# hev-controller_1_1.net
KiCad netlist of a schematic drawn in EAGLE
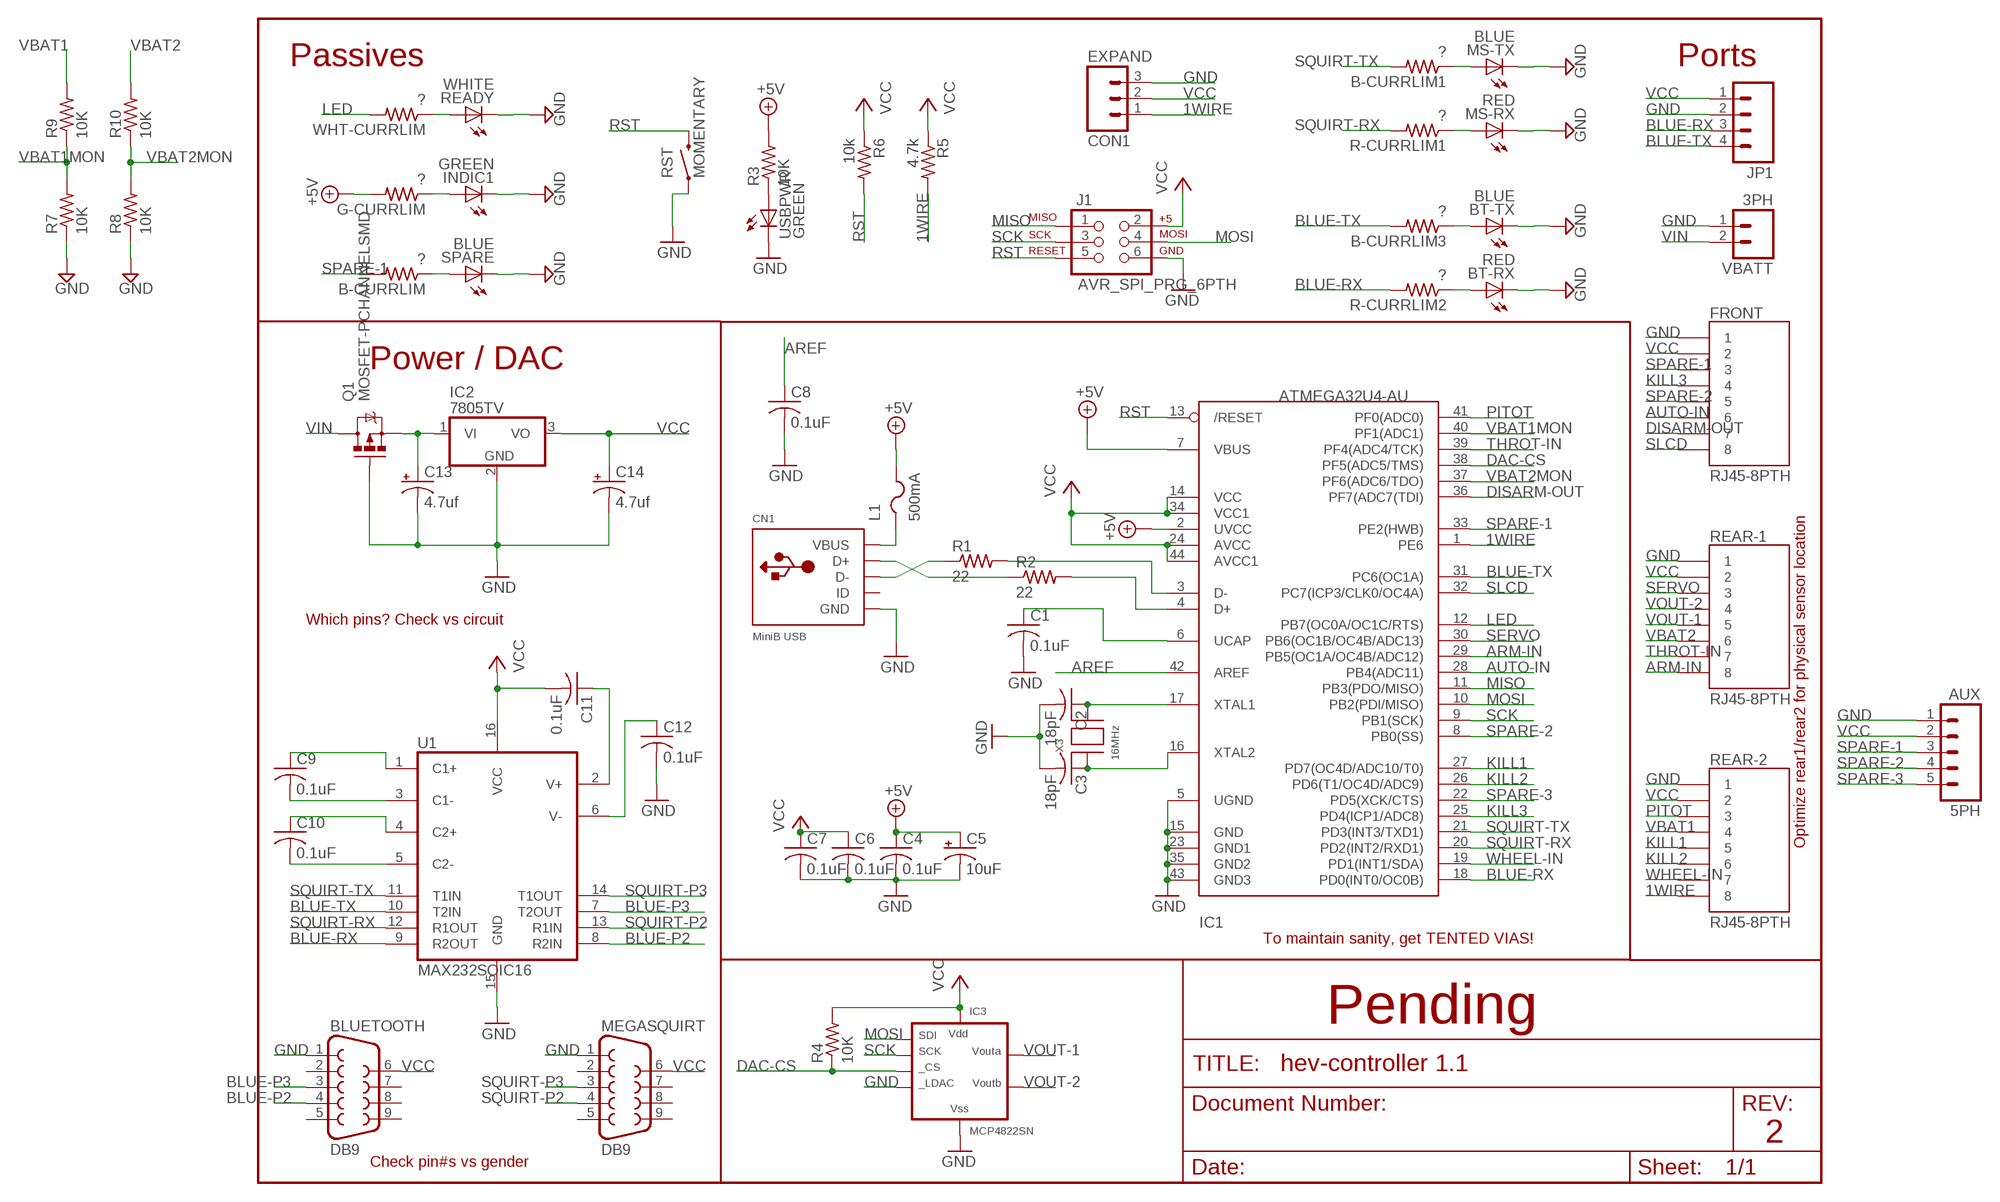
[diagram p0: schematic, sheet 1]

(export (version "E")
  (design (tool "Eeschema 10.0.6"))
  (components
    (comp (ref "5PH")
      (value "AUX")
      (footprint "eagle-import:1X05")
      (libsource (lib "eagle-import") (part "M05PTH"))
    )
    (comp (ref "B-CURRLIM")
      (value "?")
      (footprint "eagle-import:R0805")
      (libsource (lib "eagle-import") (part "R-US_R0805"))
    )
    (comp (ref "B-CURRLIM1")
      (value "?")
      (footprint "eagle-import:R0805")
      (libsource (lib "eagle-import") (part "R-US_R0805"))
    )
    (comp (ref "B-CURRLIM3")
      (value "?")
      (footprint "eagle-import:R0805")
      (libsource (lib "eagle-import") (part "R-US_R0805"))
    )
    (comp (ref "BLUETOOTH")
      (value "DB9")
      (footprint "eagle-import:DB9")
      (libsource (lib "eagle-import") (part "DB9"))
    )
    (comp (ref "BT-RX")
      (value "RED")
      (footprint "eagle-import:CHIPLED_0805")
      (libsource (lib "eagle-import") (part "LEDCHIPLED_0805"))
    )
    (comp (ref "BT-TX")
      (value "BLUE")
      (footprint "eagle-import:CHIPLED_0805")
      (libsource (lib "eagle-import") (part "LEDCHIPLED_0805"))
    )
    (comp (ref "C1")
      (value "0.1uF")
      (footprint "eagle-import:C0805K")
      (libsource (lib "eagle-import") (part "C-USC0805K"))
    )
    (comp (ref "C2")
      (value "18pF")
      (footprint "eagle-import:C0805K")
      (libsource (lib "eagle-import") (part "C-USC0805K"))
    )
    (comp (ref "C3")
      (value "18pF")
      (footprint "eagle-import:C0805K")
      (libsource (lib "eagle-import") (part "C-USC0805K"))
    )
    (comp (ref "C4")
      (value "0.1uF")
      (footprint "eagle-import:C0805K")
      (libsource (lib "eagle-import") (part "C-USC0805K"))
    )
    (comp (ref "C5")
      (value "10uF")
      (footprint "eagle-import:A_3216-18R")
      (libsource (lib "eagle-import") (part "CPOL-USA/3216-18R"))
    )
    (comp (ref "C6")
      (value "0.1uF")
      (footprint "eagle-import:C0805K")
      (libsource (lib "eagle-import") (part "C-USC0805K"))
    )
    (comp (ref "C7")
      (value "0.1uF")
      (footprint "eagle-import:C0805K")
      (libsource (lib "eagle-import") (part "C-USC0805K"))
    )
    (comp (ref "C8")
      (value "0.1uF")
      (footprint "eagle-import:C0805K")
      (libsource (lib "eagle-import") (part "C-USC0805K"))
    )
    (comp (ref "C9")
      (value "0.1uF")
      (footprint "eagle-import:C0805K")
      (libsource (lib "eagle-import") (part "C-USC0805K"))
    )
    (comp (ref "C10")
      (value "0.1uF")
      (footprint "eagle-import:C0805K")
      (libsource (lib "eagle-import") (part "C-USC0805K"))
    )
    (comp (ref "C11")
      (value "0.1uF")
      (footprint "eagle-import:C0805K")
      (libsource (lib "eagle-import") (part "C-USC0805K"))
    )
    (comp (ref "C12")
      (value "0.1uF")
      (footprint "eagle-import:C0805K")
      (libsource (lib "eagle-import") (part "C-USC0805K"))
    )
    (comp (ref "C13")
      (value "4.7uf")
      (footprint "eagle-import:E2,5-6")
      (libsource (lib "eagle-import") (part "rcl_CPOL-USE2.5-6"))
    )
    (comp (ref "C14")
      (value "4.7uf")
      (footprint "eagle-import:E2,5-6")
      (libsource (lib "eagle-import") (part "rcl_CPOL-USE2.5-6"))
    )
    (comp (ref "CN1")
      (value "MiniB USB")
      (footprint "eagle-import:USB-MINIB")
      (libsource (lib "eagle-import") (part "USBMINIB"))
    )
    (comp (ref "EXPAND")
      (value "CON1")
      (footprint "eagle-import:MOLEX-1X3")
      (libsource (lib "eagle-import") (part "M03POLAR"))
    )
    (comp (ref "FRONT")
      (value "RJ45-8PTH")
      (footprint "eagle-import:RJ45-8")
      (libsource (lib "eagle-import") (part "RJ45-8PTH"))
    )
    (comp (ref "G-CURRLIM")
      (value "?")
      (footprint "eagle-import:R0805")
      (libsource (lib "eagle-import") (part "R-US_R0805"))
    )
    (comp (ref "IC1")
      (value "ATMEGA32U4-AU")
      (footprint "eagle-import:TQFP44")
      (libsource (lib "eagle-import") (part "ATMEGA32U4-AU"))
    )
    (comp (ref "IC2")
      (value "7805TV")
      (footprint "eagle-import:TO220V")
      (libsource (lib "eagle-import") (part "78TV05"))
    )
    (comp (ref "IC3")
      (value "MCP4822SN")
      (footprint "eagle-import:SO-08")
      (libsource (lib "eagle-import") (part "MCP4822SN"))
    )
    (comp (ref "INDIC1")
      (value "GREEN")
      (footprint "eagle-import:CHIPLED_0805")
      (libsource (lib "eagle-import") (part "LEDCHIPLED_0805"))
    )
    (comp (ref "J1")
      (value "AVR_SPI_PRG_6PTH")
      (footprint "eagle-import:2X3")
      (libsource (lib "eagle-import") (part "AVR_SPI_PRG_6PTH"))
    )
    (comp (ref "JP1")
      (value "M04PTH")
      (footprint "eagle-import:1X04")
      (libsource (lib "eagle-import") (part "M04PTH"))
    )
    (comp (ref "L1")
      (value "500mA")
      (footprint "eagle-import:R1206")
      (libsource (lib "eagle-import") (part "PTCFUSE-1206"))
    )
    (comp (ref "MEGASQUIRT")
      (value "DB9")
      (footprint "eagle-import:DB9")
      (libsource (lib "eagle-import") (part "DB9"))
    )
    (comp (ref "MS-RX")
      (value "RED")
      (footprint "eagle-import:CHIPLED_0805")
      (libsource (lib "eagle-import") (part "LEDCHIPLED_0805"))
    )
    (comp (ref "MS-TX")
      (value "BLUE")
      (footprint "eagle-import:CHIPLED_0805")
      (libsource (lib "eagle-import") (part "LEDCHIPLED_0805"))
    )
    (comp (ref "Q1")
      (value "MOSFET-PCHANNELSMD")
      (footprint "eagle-import:SOT23-3")
      (libsource (lib "eagle-import") (part "MOSFET-PCHANNELSMD"))
    )
    (comp (ref "R-CURRLIM1")
      (value "?")
      (footprint "eagle-import:R0805")
      (libsource (lib "eagle-import") (part "R-US_R0805"))
    )
    (comp (ref "R-CURRLIM2")
      (value "?")
      (footprint "eagle-import:R0805")
      (libsource (lib "eagle-import") (part "R-US_R0805"))
    )
    (comp (ref "R1")
      (value "22")
      (footprint "eagle-import:R0805")
      (libsource (lib "eagle-import") (part "R-US_R0805"))
    )
    (comp (ref "R2")
      (value "22")
      (footprint "eagle-import:R0805")
      (libsource (lib "eagle-import") (part "R-US_R0805"))
    )
    (comp (ref "R3")
      (value "10K")
      (footprint "eagle-import:R0805")
      (libsource (lib "eagle-import") (part "R-US_R0805"))
    )
    (comp (ref "R4")
      (value "10K")
      (footprint "eagle-import:R0805")
      (libsource (lib "eagle-import") (part "R-US_R0805"))
    )
    (comp (ref "R5")
      (value "4.7k")
      (footprint "eagle-import:R0805")
      (libsource (lib "eagle-import") (part "R-US_R0805"))
    )
    (comp (ref "R6")
      (value "10k")
      (footprint "eagle-import:R0805")
      (libsource (lib "eagle-import") (part "R-US_R0805"))
    )
    (comp (ref "R7")
      (value "10K")
      (footprint "eagle-import:R0805")
      (libsource (lib "eagle-import") (part "R-US_R0805"))
    )
    (comp (ref "R8")
      (value "10K")
      (footprint "eagle-import:R0805")
      (libsource (lib "eagle-import") (part "R-US_R0805"))
    )
    (comp (ref "R9")
      (value "10K")
      (footprint "eagle-import:R0805")
      (libsource (lib "eagle-import") (part "R-US_R0805"))
    )
    (comp (ref "R10")
      (value "10K")
      (footprint "eagle-import:R0805")
      (libsource (lib "eagle-import") (part "R-US_R0805"))
    )
    (comp (ref "READY")
      (value "WHITE")
      (footprint "eagle-import:LED-1206")
      (libsource (lib "eagle-import") (part "LED1206"))
    )
    (comp (ref "REAR-1")
      (value "RJ45-8PTH")
      (footprint "eagle-import:RJ45-8")
      (libsource (lib "eagle-import") (part "RJ45-8PTH"))
    )
    (comp (ref "REAR-2")
      (value "RJ45-8PTH")
      (footprint "eagle-import:RJ45-8")
      (libsource (lib "eagle-import") (part "RJ45-8PTH"))
    )
    (comp (ref "RST")
      (value "MOMENTARY")
      (footprint "eagle-import:TACTILE-SWITCH-1101NE")
      (libsource (lib "eagle-import") (part "SWITCH-MOMENTARY-2-SMD-1101NE"))
    )
    (comp (ref "SPARE")
      (value "BLUE")
      (footprint "eagle-import:CHIPLED_0805")
      (libsource (lib "eagle-import") (part "LEDCHIPLED_0805"))
    )
    (comp (ref "U1")
      (value "MAX232SOIC16")
      (footprint "eagle-import:SO016")
      (libsource (lib "eagle-import") (part "MAX232SOIC16"))
    )
    (comp (ref "USBPWR")
      (value "GREEN")
      (footprint "eagle-import:CHIPLED_0805")
      (libsource (lib "eagle-import") (part "LEDCHIPLED_0805"))
    )
    (comp (ref "VBATT")
      (value "3PH")
      (footprint "eagle-import:SCREWTERMINAL-3.5MM-2")
      (libsource (lib "eagle-import") (part "M023.5MM"))
    )
    (comp (ref "WHT-CURRLIM")
      (value "?")
      (footprint "eagle-import:R0805")
      (libsource (lib "eagle-import") (part "R-US_R0805"))
    )
    (comp (ref "X3")
      (value "16MHz")
      (footprint "eagle-import:NX5032")
      (libsource (lib "eagle-import") (part "XTALNX5032"))
    )
  )
  (nets
    (net (code "1") (name "+5V") (class "Default")
      (node (ref "C4") (pin "1") (pinfunction "1_1") (pintype "passive"))
      (node (ref "C5") (pin "+") (pinfunction "+_+") (pintype "passive"))
      (node (ref "G-CURRLIM") (pin "2") (pinfunction "2_2") (pintype "passive"))
      (node (ref "IC1") (pin "2") (pinfunction "UVCC_2") (pintype "bidirectional"))
      (node (ref "IC1") (pin "7") (pinfunction "VBUS_7") (pintype "bidirectional"))
      (node (ref "L1") (pin "2") (pinfunction "2_2") (pintype "passive"))
      (node (ref "R3") (pin "2") (pinfunction "2_2") (pintype "passive"))
    )
    (net (code "2") (name "/1WIRE") (class "Default")
      (node (ref "EXPAND") (pin "1") (pinfunction "1_1") (pintype "passive"))
      (node (ref "IC1") (pin "1") (pinfunction "PE6_1") (pintype "bidirectional"))
      (node (ref "R5") (pin "2") (pinfunction "2_2") (pintype "passive"))
      (node (ref "REAR-2") (pin "8") (pinfunction "8_8") (pintype "bidirectional"))
    )
    (net (code "3") (name "/AREF") (class "Default")
      (node (ref "C8") (pin "1") (pinfunction "1_1") (pintype "passive"))
      (node (ref "IC1") (pin "42") (pinfunction "AREF_42") (pintype "bidirectional"))
    )
    (net (code "4") (name "/ARM-IN") (class "Default")
      (node (ref "IC1") (pin "29") (pinfunction "PB5(OC1A/OC4B/ADC12)_29") (pintype "bidirectional"))
      (node (ref "REAR-1") (pin "8") (pinfunction "8_8") (pintype "bidirectional"))
    )
    (net (code "5") (name "/AUTO-IN") (class "Default")
      (node (ref "FRONT") (pin "6") (pinfunction "6_6") (pintype "bidirectional"))
      (node (ref "IC1") (pin "28") (pinfunction "PB4(ADC11)_28") (pintype "bidirectional"))
    )
    (net (code "6") (name "/BLUE-P2") (class "Default")
      (node (ref "BLUETOOTH") (pin "4") (pinfunction "4_4") (pintype "passive"))
      (node (ref "U1") (pin "8") (pinfunction "R2IN_8") (pintype "input"))
    )
    (net (code "7") (name "/BLUE-P3") (class "Default")
      (node (ref "BLUETOOTH") (pin "3") (pinfunction "3_3") (pintype "passive"))
      (node (ref "U1") (pin "7") (pinfunction "T2OUT_7") (pintype "output"))
    )
    (net (code "8") (name "/BLUE-RX") (class "Default")
      (node (ref "IC1") (pin "18") (pinfunction "PD0(INT0/OC0B)_18") (pintype "bidirectional"))
      (node (ref "JP1") (pin "3") (pinfunction "3_3") (pintype "passive"))
      (node (ref "R-CURRLIM2") (pin "2") (pinfunction "2_2") (pintype "passive"))
      (node (ref "U1") (pin "9") (pinfunction "R2OUT_9") (pintype "output"))
    )
    (net (code "9") (name "/BLUE-TX") (class "Default")
      (node (ref "B-CURRLIM3") (pin "2") (pinfunction "2_2") (pintype "passive"))
      (node (ref "IC1") (pin "31") (pinfunction "PC6(OC1A)_31") (pintype "bidirectional"))
      (node (ref "JP1") (pin "4") (pinfunction "4_4") (pintype "passive"))
      (node (ref "U1") (pin "10") (pinfunction "T2IN_10") (pintype "input"))
    )
    (net (code "10") (name "/DAC-CS") (class "Default")
      (node (ref "IC1") (pin "38") (pinfunction "PF5(ADC5/TMS)_38") (pintype "bidirectional"))
      (node (ref "IC3") (pin "2") (pinfunction "CS_2") (pintype "input"))
      (node (ref "R4") (pin "1") (pinfunction "1_1") (pintype "passive"))
    )
    (net (code "11") (name "/DISARM-OUT") (class "Default")
      (node (ref "FRONT") (pin "7") (pinfunction "7_7") (pintype "bidirectional"))
      (node (ref "IC1") (pin "36") (pinfunction "PF7(ADC7(TDI)_36") (pintype "bidirectional"))
    )
    (net (code "12") (name "/KILL1") (class "Default")
      (node (ref "IC1") (pin "27") (pinfunction "PD7(OC4D/ADC10/T0)_27") (pintype "bidirectional"))
      (node (ref "REAR-2") (pin "5") (pinfunction "5_5") (pintype "bidirectional"))
    )
    (net (code "13") (name "/KILL2") (class "Default")
      (node (ref "IC1") (pin "26") (pinfunction "PD6(T1/OC4D/ADC9)_26") (pintype "bidirectional"))
      (node (ref "REAR-2") (pin "6") (pinfunction "6_6") (pintype "bidirectional"))
    )
    (net (code "14") (name "/KILL3") (class "Default")
      (node (ref "FRONT") (pin "4") (pinfunction "4_4") (pintype "bidirectional"))
      (node (ref "IC1") (pin "25") (pinfunction "PD4(ICP1/ADC8)_25") (pintype "bidirectional"))
    )
    (net (code "15") (name "/LED") (class "Default")
      (node (ref "IC1") (pin "12") (pinfunction "PB7(OC0A/OC1C/RTS)_12") (pintype "bidirectional"))
      (node (ref "WHT-CURRLIM") (pin "2") (pinfunction "2_2") (pintype "passive"))
    )
    (net (code "16") (name "/MISO") (class "Default")
      (node (ref "IC1") (pin "11") (pinfunction "PB3(PDO/MISO)_11") (pintype "bidirectional"))
      (node (ref "J1") (pin "1") (pinfunction "1_1") (pintype "passive"))
    )
    (net (code "17") (name "/MOSI") (class "Default")
      (node (ref "IC1") (pin "10") (pinfunction "PB2(PDI/MISO)_10") (pintype "bidirectional"))
      (node (ref "IC3") (pin "4") (pinfunction "SDI_4") (pintype "input"))
      (node (ref "J1") (pin "4") (pinfunction "4_4") (pintype "passive"))
    )
    (net (code "18") (name "/PITOT") (class "Default")
      (node (ref "IC1") (pin "41") (pinfunction "PF0(ADC0)_41") (pintype "bidirectional"))
      (node (ref "REAR-2") (pin "3") (pinfunction "3_3") (pintype "bidirectional"))
    )
    (net (code "19") (name "/RST") (class "Default")
      (node (ref "IC1") (pin "13") (pinfunction "/RESET_13") (pintype "bidirectional"))
      (node (ref "J1") (pin "5") (pinfunction "5_5") (pintype "passive"))
      (node (ref "R6") (pin "2") (pinfunction "2_2") (pintype "passive"))
      (node (ref "RST") (pin "P$2") (pinfunction "2_P$2") (pintype "passive"))
    )
    (net (code "20") (name "/SCK") (class "Default")
      (node (ref "IC1") (pin "9") (pinfunction "PB1(SCK)_9") (pintype "bidirectional"))
      (node (ref "IC3") (pin "3") (pinfunction "SCK_3") (pintype "input"))
      (node (ref "J1") (pin "3") (pinfunction "3_3") (pintype "passive"))
    )
    (net (code "21") (name "/SERVO") (class "Default")
      (node (ref "IC1") (pin "30") (pinfunction "PB6(OC1B/OC4B/ADC13)_30") (pintype "bidirectional"))
      (node (ref "REAR-1") (pin "3") (pinfunction "3_3") (pintype "bidirectional"))
    )
    (net (code "22") (name "/SLCD") (class "Default")
      (node (ref "FRONT") (pin "8") (pinfunction "8_8") (pintype "bidirectional"))
      (node (ref "IC1") (pin "32") (pinfunction "PC7(ICP3/CLK0/OC4A)_32") (pintype "bidirectional"))
    )
    (net (code "23") (name "/SPARE-1") (class "Default")
      (node (ref "5PH") (pin "3") (pinfunction "3_3") (pintype "passive"))
      (node (ref "B-CURRLIM") (pin "2") (pinfunction "2_2") (pintype "passive"))
      (node (ref "FRONT") (pin "3") (pinfunction "3_3") (pintype "bidirectional"))
      (node (ref "IC1") (pin "33") (pinfunction "PE2(HWB)_33") (pintype "bidirectional"))
    )
    (net (code "24") (name "/SPARE-2") (class "Default")
      (node (ref "5PH") (pin "4") (pinfunction "4_4") (pintype "passive"))
      (node (ref "FRONT") (pin "5") (pinfunction "5_5") (pintype "bidirectional"))
      (node (ref "IC1") (pin "8") (pinfunction "PB0(SS)_8") (pintype "bidirectional"))
    )
    (net (code "25") (name "/SPARE-3") (class "Default")
      (node (ref "5PH") (pin "5") (pinfunction "5_5") (pintype "passive"))
      (node (ref "IC1") (pin "22") (pinfunction "PD5(XCK/CTS)_22") (pintype "bidirectional"))
    )
    (net (code "26") (name "/SQUIRT-P2") (class "Default")
      (node (ref "MEGASQUIRT") (pin "4") (pinfunction "4_4") (pintype "passive"))
      (node (ref "U1") (pin "13") (pinfunction "R1IN_13") (pintype "input"))
    )
    (net (code "27") (name "/SQUIRT-P3") (class "Default")
      (node (ref "MEGASQUIRT") (pin "3") (pinfunction "3_3") (pintype "passive"))
      (node (ref "U1") (pin "14") (pinfunction "T1OUT_14") (pintype "output"))
    )
    (net (code "28") (name "/SQUIRT-RX") (class "Default")
      (node (ref "IC1") (pin "20") (pinfunction "PD2(INT2/RXD1)_20") (pintype "bidirectional"))
      (node (ref "R-CURRLIM1") (pin "2") (pinfunction "2_2") (pintype "passive"))
      (node (ref "U1") (pin "12") (pinfunction "R1OUT_12") (pintype "output"))
    )
    (net (code "29") (name "/SQUIRT-TX") (class "Default")
      (node (ref "B-CURRLIM1") (pin "2") (pinfunction "2_2") (pintype "passive"))
      (node (ref "IC1") (pin "21") (pinfunction "PD3(INT3/TXD1)_21") (pintype "bidirectional"))
      (node (ref "U1") (pin "11") (pinfunction "T1IN_11") (pintype "input"))
    )
    (net (code "30") (name "/THROT-IN") (class "Default")
      (node (ref "IC1") (pin "39") (pinfunction "PF4(ADC4/TCK)_39") (pintype "bidirectional"))
      (node (ref "REAR-1") (pin "7") (pinfunction "7_7") (pintype "bidirectional"))
    )
    (net (code "31") (name "/VBAT1") (class "Default")
      (node (ref "R9") (pin "2") (pinfunction "2_2") (pintype "passive"))
      (node (ref "REAR-2") (pin "4") (pinfunction "4_4") (pintype "bidirectional"))
    )
    (net (code "32") (name "/VBAT1MON") (class "Default")
      (node (ref "IC1") (pin "40") (pinfunction "PF1(ADC1)_40") (pintype "bidirectional"))
      (node (ref "R7") (pin "2") (pinfunction "2_2") (pintype "passive"))
      (node (ref "R9") (pin "1") (pinfunction "1_1") (pintype "passive"))
    )
    (net (code "33") (name "/VBAT2") (class "Default")
      (node (ref "R10") (pin "2") (pinfunction "2_2") (pintype "passive"))
      (node (ref "REAR-1") (pin "6") (pinfunction "6_6") (pintype "bidirectional"))
    )
    (net (code "34") (name "/VBAT2MON") (class "Default")
      (node (ref "IC1") (pin "37") (pinfunction "PF6(ADC6/TDO)_37") (pintype "bidirectional"))
      (node (ref "R10") (pin "1") (pinfunction "1_1") (pintype "passive"))
      (node (ref "R8") (pin "2") (pinfunction "2_2") (pintype "passive"))
    )
    (net (code "35") (name "/VIN") (class "Default")
      (node (ref "Q1") (pin "3") (pinfunction "D_3") (pintype "passive"))
      (node (ref "VBATT") (pin "2") (pinfunction "2_2") (pintype "passive"))
    )
    (net (code "36") (name "/VOUT-1") (class "Default")
      (node (ref "IC3") (pin "8") (pinfunction "VOUTA_8") (pintype "output"))
      (node (ref "REAR-1") (pin "5") (pinfunction "5_5") (pintype "bidirectional"))
    )
    (net (code "37") (name "/VOUT-2") (class "Default")
      (node (ref "IC3") (pin "6") (pinfunction "VOUTB_6") (pintype "output"))
      (node (ref "REAR-1") (pin "4") (pinfunction "4_4") (pintype "bidirectional"))
    )
    (net (code "38") (name "/WHEEL-IN") (class "Default")
      (node (ref "IC1") (pin "19") (pinfunction "PD1(INT1/SDA)_19") (pintype "bidirectional"))
      (node (ref "REAR-2") (pin "7") (pinfunction "7_7") (pintype "bidirectional"))
    )
    (net (code "39") (name "GND") (class "Default")
      (node (ref "5PH") (pin "1") (pinfunction "1_1") (pintype "passive"))
      (node (ref "BLUETOOTH") (pin "1") (pinfunction "1_1") (pintype "passive"))
      (node (ref "BT-RX") (pin "C") (pinfunction "C_C") (pintype "passive"))
      (node (ref "BT-TX") (pin "C") (pinfunction "C_C") (pintype "passive"))
      (node (ref "C1") (pin "2") (pinfunction "2_2") (pintype "passive"))
      (node (ref "C12") (pin "2") (pinfunction "2_2") (pintype "passive"))
      (node (ref "C13") (pin "-") (pinfunction "-_-") (pintype "passive"))
      (node (ref "C14") (pin "-") (pinfunction "-_-") (pintype "passive"))
      (node (ref "C2") (pin "2") (pinfunction "2_2") (pintype "passive"))
      (node (ref "C3") (pin "2") (pinfunction "2_2") (pintype "passive"))
      (node (ref "C4") (pin "2") (pinfunction "2_2") (pintype "passive"))
      (node (ref "C5") (pin "-") (pinfunction "-_-") (pintype "passive"))
      (node (ref "C6") (pin "2") (pinfunction "2_2") (pintype "passive"))
      (node (ref "C7") (pin "2") (pinfunction "2_2") (pintype "passive"))
      (node (ref "C8") (pin "2") (pinfunction "2_2") (pintype "passive"))
      (node (ref "CN1") (pin "GND") (pinfunction "GND_GND") (pintype "power_in"))
      (node (ref "EXPAND") (pin "3") (pinfunction "3_3") (pintype "passive"))
      (node (ref "FRONT") (pin "1") (pinfunction "1_1") (pintype "bidirectional"))
      (node (ref "IC1") (pin "15") (pinfunction "GND_15") (pintype "bidirectional"))
      (node (ref "IC1") (pin "23") (pinfunction "GND1_23") (pintype "bidirectional"))
      (node (ref "IC1") (pin "35") (pinfunction "GND2_35") (pintype "bidirectional"))
      (node (ref "IC1") (pin "43") (pinfunction "GND3_43") (pintype "bidirectional"))
      (node (ref "IC1") (pin "5") (pinfunction "UGND_5") (pintype "bidirectional"))
      (node (ref "IC2") (pin "2") (pinfunction "GND_2") (pintype "passive"))
      (node (ref "IC3") (pin "5") (pinfunction "LDAC_5") (pintype "input"))
      (node (ref "IC3") (pin "7") (pinfunction "VSS_7") (pintype "power_in"))
      (node (ref "INDIC1") (pin "C") (pinfunction "C_C") (pintype "passive"))
      (node (ref "J1") (pin "6") (pinfunction "6_6") (pintype "passive"))
      (node (ref "JP1") (pin "2") (pinfunction "2_2") (pintype "passive"))
      (node (ref "MEGASQUIRT") (pin "1") (pinfunction "1_1") (pintype "passive"))
      (node (ref "MS-RX") (pin "C") (pinfunction "C_C") (pintype "passive"))
      (node (ref "MS-TX") (pin "C") (pinfunction "C_C") (pintype "passive"))
      (node (ref "Q1") (pin "1") (pinfunction "G_1") (pintype "passive"))
      (node (ref "R7") (pin "1") (pinfunction "1_1") (pintype "passive"))
      (node (ref "R8") (pin "1") (pinfunction "1_1") (pintype "passive"))
      (node (ref "READY") (pin "C") (pinfunction "C_C") (pintype "passive"))
      (node (ref "REAR-1") (pin "1") (pinfunction "1_1") (pintype "bidirectional"))
      (node (ref "REAR-2") (pin "1") (pinfunction "1_1") (pintype "bidirectional"))
      (node (ref "RST") (pin "P$1") (pinfunction "1_P$1") (pintype "passive"))
      (node (ref "SPARE") (pin "C") (pinfunction "C_C") (pintype "passive"))
      (node (ref "U1") (pin "15") (pinfunction "GND_15") (pintype "bidirectional"))
      (node (ref "USBPWR") (pin "C") (pinfunction "C_C") (pintype "passive"))
      (node (ref "VBATT") (pin "1") (pinfunction "1_1") (pintype "passive"))
    )
    (net (code "40") (name "Net-(B-CURRLIM-Pad1)") (class "Default")
      (node (ref "B-CURRLIM") (pin "1") (pinfunction "1_1") (pintype "passive"))
      (node (ref "SPARE") (pin "A") (pinfunction "A_A") (pintype "passive"))
    )
    (net (code "41") (name "Net-(B-CURRLIM1-Pad1)") (class "Default")
      (node (ref "B-CURRLIM1") (pin "1") (pinfunction "1_1") (pintype "passive"))
      (node (ref "MS-TX") (pin "A") (pinfunction "A_A") (pintype "passive"))
    )
    (net (code "42") (name "Net-(B-CURRLIM3-Pad1)") (class "Default")
      (node (ref "B-CURRLIM3") (pin "1") (pinfunction "1_1") (pintype "passive"))
      (node (ref "BT-TX") (pin "A") (pinfunction "A_A") (pintype "passive"))
    )
    (net (code "43") (name "Net-(BT-RX-PadA)") (class "Default")
      (node (ref "BT-RX") (pin "A") (pinfunction "A_A") (pintype "passive"))
      (node (ref "R-CURRLIM2") (pin "1") (pinfunction "1_1") (pintype "passive"))
    )
    (net (code "44") (name "Net-(CN1-PadD+)") (class "Default")
      (node (ref "CN1") (pin "D+") (pinfunction "D+_D+") (pintype "bidirectional"))
      (node (ref "R2") (pin "1") (pinfunction "1_1") (pintype "passive"))
    )
    (net (code "45") (name "Net-(CN1-PadD-)") (class "Default")
      (node (ref "CN1") (pin "D-") (pinfunction "D-_D-") (pintype "bidirectional"))
      (node (ref "R1") (pin "1") (pinfunction "1_1") (pintype "passive"))
    )
    (net (code "46") (name "Net-(CN1-PadVBUS)") (class "Default")
      (node (ref "CN1") (pin "VBUS") (pinfunction "VBUS_VBUS") (pintype "power_in"))
      (node (ref "L1") (pin "1") (pinfunction "1_1") (pintype "passive"))
    )
    (net (code "47") (name "Net-(G-CURRLIM-Pad1)") (class "Default")
      (node (ref "G-CURRLIM") (pin "1") (pinfunction "1_1") (pintype "passive"))
      (node (ref "INDIC1") (pin "A") (pinfunction "A_A") (pintype "passive"))
    )
    (net (code "48") (name "Net-(IC1-D+)") (class "Default")
      (node (ref "IC1") (pin "4") (pinfunction "D+_4") (pintype "bidirectional"))
      (node (ref "R2") (pin "2") (pinfunction "2_2") (pintype "passive"))
    )
    (net (code "49") (name "Net-(IC1-D-)") (class "Default")
      (node (ref "IC1") (pin "3") (pinfunction "D-_3") (pintype "bidirectional"))
      (node (ref "R1") (pin "2") (pinfunction "2_2") (pintype "passive"))
    )
    (net (code "50") (name "Net-(IC1-UCAP)") (class "Default")
      (node (ref "C1") (pin "1") (pinfunction "1_1") (pintype "passive"))
      (node (ref "IC1") (pin "6") (pinfunction "UCAP_6") (pintype "bidirectional"))
    )
    (net (code "51") (name "Net-(IC1-XTAL1)") (class "Default")
      (node (ref "C2") (pin "1") (pinfunction "1_1") (pintype "passive"))
      (node (ref "IC1") (pin "17") (pinfunction "XTAL1_17") (pintype "bidirectional"))
      (node (ref "X3") (pin "P$2") (pinfunction "P$2_P$2") (pintype "bidirectional"))
    )
    (net (code "52") (name "Net-(IC1-XTAL2)") (class "Default")
      (node (ref "C3") (pin "1") (pinfunction "1_1") (pintype "passive"))
      (node (ref "IC1") (pin "16") (pinfunction "XTAL2_16") (pintype "bidirectional"))
      (node (ref "X3") (pin "P$1") (pinfunction "P$1_P$1") (pintype "bidirectional"))
    )
    (net (code "53") (name "Net-(IC2-VI)") (class "Default")
      (node (ref "C13") (pin "+") (pinfunction "+_+") (pintype "passive"))
      (node (ref "IC2") (pin "1") (pinfunction "VI_1") (pintype "input"))
      (node (ref "Q1") (pin "2") (pinfunction "S_2") (pintype "passive"))
    )
    (net (code "54") (name "Net-(MS-RX-PadA)") (class "Default")
      (node (ref "MS-RX") (pin "A") (pinfunction "A_A") (pintype "passive"))
      (node (ref "R-CURRLIM1") (pin "1") (pinfunction "1_1") (pintype "passive"))
    )
    (net (code "55") (name "Net-(R3-Pad1)") (class "Default")
      (node (ref "R3") (pin "1") (pinfunction "1_1") (pintype "passive"))
      (node (ref "USBPWR") (pin "A") (pinfunction "A_A") (pintype "passive"))
    )
    (net (code "56") (name "Net-(READY-PadA)") (class "Default")
      (node (ref "READY") (pin "A") (pinfunction "A_A") (pintype "passive"))
      (node (ref "WHT-CURRLIM") (pin "1") (pinfunction "1_1") (pintype "passive"))
    )
    (net (code "57") (name "Net-(U1-C1+)") (class "Default")
      (node (ref "C9") (pin "1") (pinfunction "1_1") (pintype "passive"))
      (node (ref "U1") (pin "1") (pinfunction "C1+_1") (pintype "bidirectional"))
    )
    (net (code "58") (name "Net-(U1-C1-)") (class "Default")
      (node (ref "C9") (pin "2") (pinfunction "2_2") (pintype "passive"))
      (node (ref "U1") (pin "3") (pinfunction "C1-_3") (pintype "bidirectional"))
    )
    (net (code "59") (name "Net-(U1-C2+)") (class "Default")
      (node (ref "C10") (pin "1") (pinfunction "1_1") (pintype "passive"))
      (node (ref "U1") (pin "4") (pinfunction "C2+_4") (pintype "bidirectional"))
    )
    (net (code "60") (name "Net-(U1-C2-)") (class "Default")
      (node (ref "C10") (pin "2") (pinfunction "2_2") (pintype "passive"))
      (node (ref "U1") (pin "5") (pinfunction "C2-_5") (pintype "bidirectional"))
    )
    (net (code "61") (name "Net-(U1-V+)") (class "Default")
      (node (ref "C11") (pin "1") (pinfunction "1_1") (pintype "passive"))
      (node (ref "U1") (pin "2") (pinfunction "V+_2") (pintype "bidirectional"))
    )
    (net (code "62") (name "Net-(U1-V-)") (class "Default")
      (node (ref "C12") (pin "1") (pinfunction "1_1") (pintype "passive"))
      (node (ref "U1") (pin "6") (pinfunction "V-_6") (pintype "bidirectional"))
    )
    (net (code "63") (name "VCC") (class "Default")
      (node (ref "5PH") (pin "2") (pinfunction "2_2") (pintype "passive"))
      (node (ref "BLUETOOTH") (pin "6") (pinfunction "6_6") (pintype "passive"))
      (node (ref "C11") (pin "2") (pinfunction "2_2") (pintype "passive"))
      (node (ref "C14") (pin "+") (pinfunction "+_+") (pintype "passive"))
      (node (ref "C6") (pin "1") (pinfunction "1_1") (pintype "passive"))
      (node (ref "C7") (pin "1") (pinfunction "1_1") (pintype "passive"))
      (node (ref "EXPAND") (pin "2") (pinfunction "2_2") (pintype "passive"))
      (node (ref "FRONT") (pin "2") (pinfunction "2_2") (pintype "bidirectional"))
      (node (ref "IC1") (pin "14") (pinfunction "VCC_14") (pintype "bidirectional"))
      (node (ref "IC1") (pin "24") (pinfunction "AVCC_24") (pintype "bidirectional"))
      (node (ref "IC1") (pin "34") (pinfunction "VCC1_34") (pintype "bidirectional"))
      (node (ref "IC1") (pin "44") (pinfunction "AVCC1_44") (pintype "bidirectional"))
      (node (ref "IC2") (pin "3") (pinfunction "VO_3") (pintype "passive"))
      (node (ref "IC3") (pin "1") (pinfunction "VDD_1") (pintype "power_in"))
      (node (ref "J1") (pin "2") (pinfunction "2_2") (pintype "passive"))
      (node (ref "JP1") (pin "1") (pinfunction "1_1") (pintype "passive"))
      (node (ref "MEGASQUIRT") (pin "6") (pinfunction "6_6") (pintype "passive"))
      (node (ref "R4") (pin "2") (pinfunction "2_2") (pintype "passive"))
      (node (ref "R5") (pin "1") (pinfunction "1_1") (pintype "passive"))
      (node (ref "R6") (pin "1") (pinfunction "1_1") (pintype "passive"))
      (node (ref "REAR-1") (pin "2") (pinfunction "2_2") (pintype "bidirectional"))
      (node (ref "REAR-2") (pin "2") (pinfunction "2_2") (pintype "bidirectional"))
      (node (ref "U1") (pin "16") (pinfunction "VCC_16") (pintype "bidirectional"))
    )
    (net (code "64") (name "unconnected-(BLUETOOTH-Pad2)") (class "Default")
      (node (ref "BLUETOOTH") (pin "2") (pinfunction "2_2") (pintype "passive"))
    )
    (net (code "65") (name "unconnected-(BLUETOOTH-Pad5)") (class "Default")
      (node (ref "BLUETOOTH") (pin "5") (pinfunction "5_5") (pintype "passive"))
    )
    (net (code "66") (name "unconnected-(BLUETOOTH-Pad7)") (class "Default")
      (node (ref "BLUETOOTH") (pin "7") (pinfunction "7_7") (pintype "passive"))
    )
    (net (code "67") (name "unconnected-(BLUETOOTH-Pad8)") (class "Default")
      (node (ref "BLUETOOTH") (pin "8") (pinfunction "8_8") (pintype "passive"))
    )
    (net (code "68") (name "unconnected-(BLUETOOTH-Pad9)") (class "Default")
      (node (ref "BLUETOOTH") (pin "9") (pinfunction "9_9") (pintype "passive"))
    )
    (net (code "69") (name "unconnected-(CN1-PadID)") (class "Default")
      (node (ref "CN1") (pin "ID") (pinfunction "ID_ID") (pintype "bidirectional"))
    )
    (net (code "70") (name "unconnected-(MEGASQUIRT-Pad2)") (class "Default")
      (node (ref "MEGASQUIRT") (pin "2") (pinfunction "2_2") (pintype "passive"))
    )
    (net (code "71") (name "unconnected-(MEGASQUIRT-Pad5)") (class "Default")
      (node (ref "MEGASQUIRT") (pin "5") (pinfunction "5_5") (pintype "passive"))
    )
    (net (code "72") (name "unconnected-(MEGASQUIRT-Pad7)") (class "Default")
      (node (ref "MEGASQUIRT") (pin "7") (pinfunction "7_7") (pintype "passive"))
    )
    (net (code "73") (name "unconnected-(MEGASQUIRT-Pad8)") (class "Default")
      (node (ref "MEGASQUIRT") (pin "8") (pinfunction "8_8") (pintype "passive"))
    )
    (net (code "74") (name "unconnected-(MEGASQUIRT-Pad9)") (class "Default")
      (node (ref "MEGASQUIRT") (pin "9") (pinfunction "9_9") (pintype "passive"))
    )
  )
)
